# Schematic_AlchemyBoxSimple_2024-01-02.net
KiCad netlist of a schematic drawn in Altium Designer
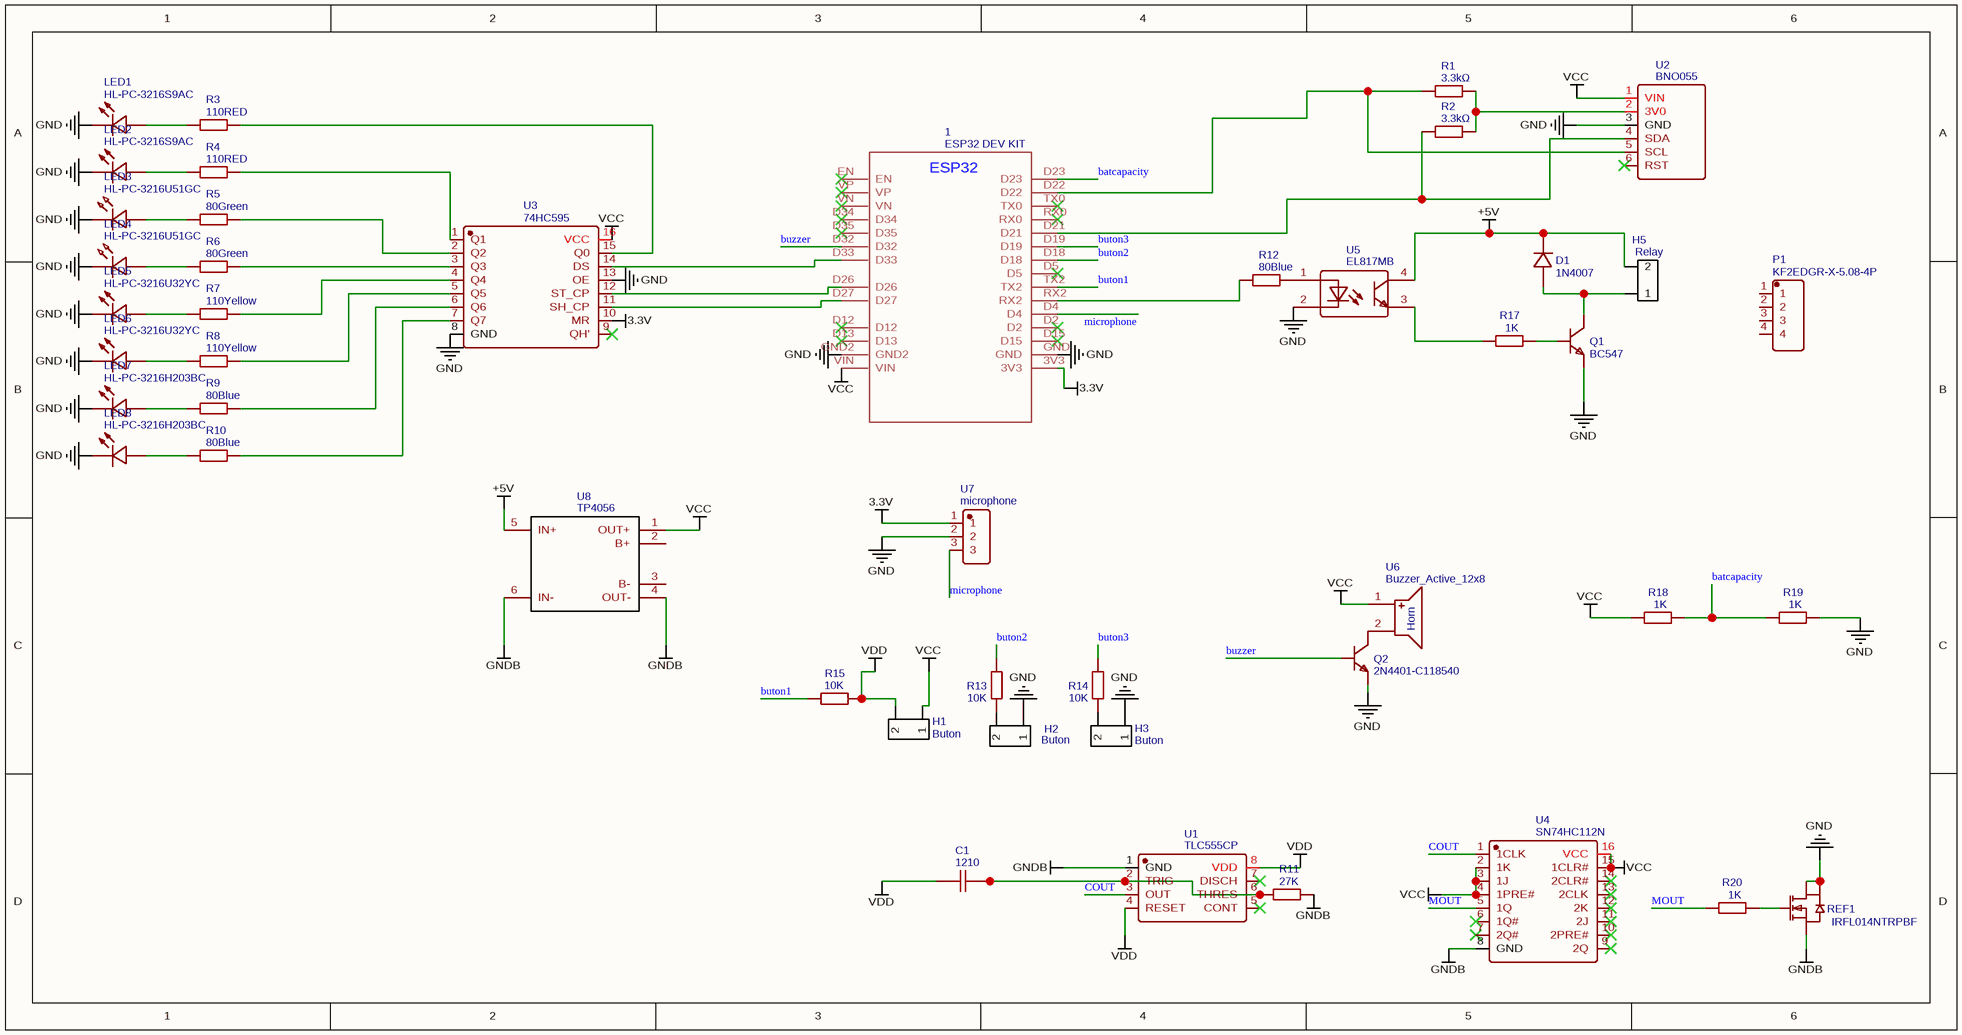
[diagram p0: Schematic_AlchemyBoxSimple_2024-01-02.schdoc]

(export (version "E")
  (design (tool "Eeschema 10.0.6"))
  (components
    (comp (ref "1")
      (value "ESP32 DEV KIT")
      (fields (field (name "CONTRIBUTOR") "u18040382"))
      (libsource (lib "altium-import") (part "root_0_ESP32 DEV KIT_"))
    )
    (comp (ref "C1")
      (value "1210")
      (fields (field (name "CONTRIBUTOR") "lcsc"))
      (libsource (lib "altium-import") (part "root_0_1210_"))
    )
    (comp (ref "D1")
      (value "1N4007")
      (fields (field (name "MANUFACTURER") "ST(先科)"))
      (libsource (lib "altium-import") (part "root_3_1N4007_"))
    )
    (comp (ref "H1")
      (value "Buton")
      (fields
        (field (name "MANUFACTURER") "BOOMELE")
        (field (name "MANUFACTURER PART") "Female headerHDR1X8-2.54")
        (field (name "CONTRIBUTOR") "kafikangi.m")
      )
      (libsource (lib "altium-import") (part "root_0_Buton_"))
    )
    (comp (ref "H2")
      (value "Buton")
      (fields
        (field (name "MANUFACTURER") "BOOMELE")
        (field (name "MANUFACTURER PART") "Female headerHDR1X8-2.54")
        (field (name "CONTRIBUTOR") "kafikangi.m")
      )
      (libsource (lib "altium-import") (part "root_0_Buton_"))
    )
    (comp (ref "H3")
      (value "Buton")
      (fields
        (field (name "MANUFACTURER") "BOOMELE")
        (field (name "MANUFACTURER PART") "Female headerHDR1X8-2.54")
        (field (name "CONTRIBUTOR") "kafikangi.m")
      )
      (libsource (lib "altium-import") (part "root_0_Buton_"))
    )
    (comp (ref "H5")
      (value "Relay")
      (fields
        (field (name "MANUFACTURER") "BOOMELE")
        (field (name "MANUFACTURER PART") "Female headerHDR1X8-2.54")
        (field (name "CONTRIBUTOR") "kafikangi.m")
      )
      (libsource (lib "altium-import") (part "root_1_Relay_"))
    )
    (comp (ref "LED1")
      (value "HL-PC-3216S9AC")
      (fields (field (name "MANUFACTURER") "HONGLITRONIC(鸿利光电)") (field (name "CONTRIBUTOR") "edfed"))
      (libsource (lib "altium-import") (part "root_0_HL-PC-3216S9AC_"))
    )
    (comp (ref "LED2")
      (value "HL-PC-3216S9AC")
      (fields (field (name "MANUFACTURER") "HONGLITRONIC(鸿利光电)") (field (name "CONTRIBUTOR") "edfed"))
      (libsource (lib "altium-import") (part "root_0_HL-PC-3216S9AC_"))
    )
    (comp (ref "LED3")
      (value "HL-PC-3216U51GC")
      (fields (field (name "MANUFACTURER") "HONGLITRONIC(鸿利光电)") (field (name "CONTRIBUTOR") "LCSC"))
      (libsource (lib "altium-import") (part "root_0_HL-PC-3216U51GC_"))
    )
    (comp (ref "LED4")
      (value "HL-PC-3216U51GC")
      (fields (field (name "MANUFACTURER") "HONGLITRONIC(鸿利光电)") (field (name "CONTRIBUTOR") "LCSC"))
      (libsource (lib "altium-import") (part "root_0_HL-PC-3216U51GC_"))
    )
    (comp (ref "LED5")
      (value "HL-PC-3216U32YC")
      (fields (field (name "MANUFACTURER") "HONGLITRONIC(鸿利光电)") (field (name "CONTRIBUTOR") "LCSC"))
      (libsource (lib "altium-import") (part "root_0_HL-PC-3216U32YC_"))
    )
    (comp (ref "LED6")
      (value "HL-PC-3216U32YC")
      (fields (field (name "MANUFACTURER") "HONGLITRONIC(鸿利光电)") (field (name "CONTRIBUTOR") "LCSC"))
      (libsource (lib "altium-import") (part "root_0_HL-PC-3216U32YC_"))
    )
    (comp (ref "LED7")
      (value "HL-PC-3216H203BC")
      (fields (field (name "MANUFACTURER") "HONGLITRONIC(鸿利光电)") (field (name "CONTRIBUTOR") "LCSC"))
      (libsource (lib "altium-import") (part "root_0_HL-PC-3216H203BC_"))
    )
    (comp (ref "LED8")
      (value "HL-PC-3216H203BC")
      (fields (field (name "MANUFACTURER") "HONGLITRONIC(鸿利光电)") (field (name "CONTRIBUTOR") "LCSC"))
      (libsource (lib "altium-import") (part "root_0_HL-PC-3216H203BC_"))
    )
    (comp (ref "P1")
      (value "KF2EDGR-X-5.08-4P")
      (fields (field (name "CONTRIBUTOR") "LCSC"))
      (libsource (lib "altium-import") (part "root_0_KF2EDGR-X-5.08-4P_"))
    )
    (comp (ref "Q1")
      (value "BC547")
      (fields (field (name "MANUFACTURER") "CJ(江苏长电/长晶)") (field (name "CONTRIBUTOR") "LCSC"))
      (libsource (lib "altium-import") (part "root_0_BC547_"))
    )
    (comp (ref "Q2")
      (value "2N4401-C118540")
      (fields
        (field (name "MANUFACTURER") "ST(先科)")
        (field (name "MANUFACTURER PART") "2N4401")
        (field (name "CONTRIBUTOR") "立创EDA官方封装库")
      )
      (libsource (lib "altium-import") (part "root_0_2N4401-C118540_"))
    )
    (comp (ref "R1")
      (value "3.3kΩ")
      (fields
        (field (name "MANUFACTURER") "Tyohm(幸亚电阻)")
        (field (name "MANUFACTURER PART") "RMC08053.3K1%N")
        (field (name "CONTRIBUTOR") "LCSC")
      )
      (libsource (lib "altium-import") (part "root_0_3.3kΩ_"))
    )
    (comp (ref "R2")
      (value "3.3kΩ")
      (fields
        (field (name "MANUFACTURER") "Tyohm(幸亚电阻)")
        (field (name "MANUFACTURER PART") "RMC08053.3K1%N")
        (field (name "CONTRIBUTOR") "LCSC")
      )
      (libsource (lib "altium-import") (part "root_0_3.3kΩ_"))
    )
    (comp (ref "R3")
      (value "110RED")
      (fields
        (field (name "MANUFACTURER") "YAGEO(国巨)")
        (field (name "MANUFACTURER PART") "RT0805FRD07100RL")
        (field (name "CONTRIBUTOR") "LCSC")
      )
      (libsource (lib "altium-import") (part "root_0_110RED_"))
    )
    (comp (ref "R4")
      (value "110RED")
      (fields
        (field (name "MANUFACTURER") "YAGEO(国巨)")
        (field (name "MANUFACTURER PART") "RT0805FRD07100RL")
        (field (name "CONTRIBUTOR") "LCSC")
      )
      (libsource (lib "altium-import") (part "root_0_110RED_"))
    )
    (comp (ref "R5")
      (value "80Green")
      (fields
        (field (name "MANUFACTURER") "YAGEO(国巨)")
        (field (name "MANUFACTURER PART") "RT0805FRD07100RL")
        (field (name "CONTRIBUTOR") "LCSC")
      )
      (libsource (lib "altium-import") (part "root_0_80Green_"))
    )
    (comp (ref "R6")
      (value "80Green")
      (fields
        (field (name "MANUFACTURER") "YAGEO(国巨)")
        (field (name "MANUFACTURER PART") "RT0805FRD07100RL")
        (field (name "CONTRIBUTOR") "LCSC")
      )
      (libsource (lib "altium-import") (part "root_0_80Green_"))
    )
    (comp (ref "R7")
      (value "110Yellow")
      (fields
        (field (name "MANUFACTURER") "YAGEO(国巨)")
        (field (name "MANUFACTURER PART") "RT0805FRD07100RL")
        (field (name "CONTRIBUTOR") "LCSC")
      )
      (libsource (lib "altium-import") (part "root_0_110Yellow_"))
    )
    (comp (ref "R8")
      (value "110Yellow")
      (fields
        (field (name "MANUFACTURER") "YAGEO(国巨)")
        (field (name "MANUFACTURER PART") "RT0805FRD07100RL")
        (field (name "CONTRIBUTOR") "LCSC")
      )
      (libsource (lib "altium-import") (part "root_0_110Yellow_"))
    )
    (comp (ref "R9")
      (value "80Blue")
      (fields
        (field (name "MANUFACTURER") "YAGEO(国巨)")
        (field (name "MANUFACTURER PART") "RT0805FRD07100RL")
        (field (name "CONTRIBUTOR") "LCSC")
      )
      (libsource (lib "altium-import") (part "root_0_80Blue_"))
    )
    (comp (ref "R10")
      (value "80Blue")
      (fields
        (field (name "MANUFACTURER") "YAGEO(国巨)")
        (field (name "MANUFACTURER PART") "RT0805FRD07100RL")
        (field (name "CONTRIBUTOR") "LCSC")
      )
      (libsource (lib "altium-import") (part "root_0_80Blue_"))
    )
    (comp (ref "R11")
      (value "27K")
      (fields
        (field (name "MANUFACTURER") "YAGEO(国巨)")
        (field (name "MANUFACTURER PART") "RT0805FRD07100RL")
        (field (name "CONTRIBUTOR") "LCSC")
      )
      (libsource (lib "altium-import") (part "root_0_27K_"))
    )
    (comp (ref "R12")
      (value "80Blue")
      (fields
        (field (name "MANUFACTURER") "YAGEO(国巨)")
        (field (name "MANUFACTURER PART") "RT0805FRD07100RL")
        (field (name "CONTRIBUTOR") "LCSC")
      )
      (libsource (lib "altium-import") (part "root_0_80Blue_"))
    )
    (comp (ref "R13")
      (value "10K")
      (fields
        (field (name "MANUFACTURER") "YAGEO(国巨)")
        (field (name "MANUFACTURER PART") "RT0805FRD07100RL")
        (field (name "CONTRIBUTOR") "LCSC")
      )
      (libsource (lib "altium-import") (part "root_3_10K_"))
    )
    (comp (ref "R14")
      (value "10K")
      (fields
        (field (name "MANUFACTURER") "YAGEO(国巨)")
        (field (name "MANUFACTURER PART") "RT0805FRD07100RL")
        (field (name "CONTRIBUTOR") "LCSC")
      )
      (libsource (lib "altium-import") (part "root_3_10K_"))
    )
    (comp (ref "R15")
      (value "10K")
      (fields
        (field (name "MANUFACTURER") "YAGEO(国巨)")
        (field (name "MANUFACTURER PART") "RT0805FRD07100RL")
        (field (name "CONTRIBUTOR") "LCSC")
      )
      (libsource (lib "altium-import") (part "root_2_10K_"))
    )
    (comp (ref "R17")
      (value "1K")
      (fields
        (field (name "MANUFACTURER") "YAGEO(国巨)")
        (field (name "MANUFACTURER PART") "RT0805FRD07100RL")
        (field (name "CONTRIBUTOR") "LCSC")
      )
      (libsource (lib "altium-import") (part "root_2_1K_"))
    )
    (comp (ref "R18")
      (value "1K")
      (fields
        (field (name "MANUFACTURER") "YAGEO(国巨)")
        (field (name "MANUFACTURER PART") "RT0805FRD07100RL")
        (field (name "CONTRIBUTOR") "LCSC")
      )
      (libsource (lib "altium-import") (part "root_2_1K_"))
    )
    (comp (ref "R19")
      (value "1K")
      (fields
        (field (name "MANUFACTURER") "YAGEO(国巨)")
        (field (name "MANUFACTURER PART") "RT0805FRD07100RL")
        (field (name "CONTRIBUTOR") "LCSC")
      )
      (libsource (lib "altium-import") (part "root_2_1K_"))
    )
    (comp (ref "R20")
      (value "1K")
      (fields
        (field (name "MANUFACTURER") "YAGEO(国巨)")
        (field (name "MANUFACTURER PART") "RT0805FRD07100RL")
        (field (name "CONTRIBUTOR") "LCSC")
      )
      (libsource (lib "altium-import") (part "root_2_1K_"))
    )
    (comp (ref "REF1")
      (value "IRFL014NTRPBF")
      (fields (field (name "MANUFACTURER") "Infineon(英飞凌)") (field (name "CONTRIBUTOR") "lcsc"))
      (libsource (lib "altium-import") (part "root_0_IRFL014NTRPBF_"))
    )
    (comp (ref "U1")
      (value "TLC555CP")
      (fields (field (name "MANUFACTURER") "TI(德州仪器)") (field (name "CONTRIBUTOR") "LCSC"))
      (libsource (lib "altium-import") (part "root_0_TLC555CP_"))
    )
    (comp (ref "U2")
      (value "BNO055")
      (fields (field (name "CONTRIBUTOR") "thipawan2112"))
      (libsource (lib "altium-import") (part "root_0_BNO055_"))
    )
    (comp (ref "U3")
      (value "74HC595")
      (fields (field (name "CONTRIBUTOR") "Thar Lin Htin"))
      (libsource (lib "altium-import") (part "root_0_74HC595_"))
    )
    (comp (ref "U4")
      (value "SN74HC112N")
      (fields (field (name "MANUFACTURER") "TI(德州仪器)") (field (name "CONTRIBUTOR") "LCSC"))
      (libsource (lib "altium-import") (part "root_0_SN74HC112N_"))
    )
    (comp (ref "U5")
      (value "EL817MB")
      (fields (field (name "MANUFACTURER") "EVERLIGHT(亿光)") (field (name "CONTRIBUTOR") "LCSC"))
      (libsource (lib "altium-import") (part "root_0_EL817MB_"))
    )
    (comp (ref "U6")
      (value "Buzzer_Active_12x8")
      (fields (field (name "CONTRIBUTOR") "jnnganga"))
      (libsource (lib "altium-import") (part "root_0_Buzzer_Active_12x8_"))
    )
    (comp (ref "U7")
      (value "microphone")
      (fields (field (name "MANUFACTURER PART") "2.54mm-1*3P 直针") (field (name "CONTRIBUTOR") "lcsc"))
      (libsource (lib "altium-import") (part "root_0_microphone_"))
    )
    (comp (ref "U8")
      (value "TP4056")
      (fields (field (name "CONTRIBUTOR") "jonathan.rama2005"))
      (libsource (lib "altium-import") (part "root_0_TP4056_"))
    )
  )
  (nets
    (net (code "1") (name "+5V") (class "Default")
      (node (ref "D1") (pin "1") (pinfunction "K_1") (pintype "passive"))
      (node (ref "H5") (pin "2") (pinfunction "2_2") (pintype "passive"))
      (node (ref "U5") (pin "4") (pinfunction "COL_4") (pintype "passive"))
      (node (ref "U8") (pin "5") (pinfunction "IN+_5") (pintype "passive"))
    )
    (net (code "2") (name "/COUT") (class "Default")
      (node (ref "U1") (pin "3") (pinfunction "OUT_3") (pintype "passive"))
      (node (ref "U4") (pin "1") (pinfunction "1CLK_1") (pintype "passive"))
    )
    (net (code "3") (name "/MOUT") (class "Default")
      (node (ref "R20") (pin "2") (pinfunction "2_2") (pintype "passive"))
      (node (ref "U4") (pin "5") (pinfunction "1Q_5") (pintype "passive"))
    )
    (net (code "4") (name "/batcapacity") (class "Default")
      (node (ref "1") (pin "D23") (pinfunction "D23_D23") (pintype "passive"))
      (node (ref "R18") (pin "1") (pinfunction "1_1") (pintype "passive"))
      (node (ref "R19") (pin "2") (pinfunction "2_2") (pintype "passive"))
    )
    (net (code "5") (name "/buton1") (class "Default")
      (node (ref "1") (pin "TX2") (pinfunction "TX2_TX2") (pintype "passive"))
      (node (ref "R15") (pin "2") (pinfunction "2_2") (pintype "passive"))
    )
    (net (code "6") (name "/buton2") (class "Default")
      (node (ref "1") (pin "D18") (pinfunction "D18_D18") (pintype "passive"))
      (node (ref "R13") (pin "1") (pinfunction "1_1") (pintype "passive"))
    )
    (net (code "7") (name "/buton3") (class "Default")
      (node (ref "1") (pin "D19") (pinfunction "D19_D19") (pintype "passive"))
      (node (ref "R14") (pin "1") (pinfunction "1_1") (pintype "passive"))
    )
    (net (code "8") (name "/buzzer") (class "Default")
      (node (ref "1") (pin "D32") (pinfunction "D32_D32") (pintype "passive"))
      (node (ref "Q2") (pin "2") (pinfunction "B_2") (pintype "passive"))
    )
    (net (code "9") (name "/microphone") (class "Default")
      (node (ref "1") (pin "D4") (pinfunction "D4_D4") (pintype "passive"))
      (node (ref "U7") (pin "3") (pinfunction "3_3") (pintype "passive"))
    )
    (net (code "10") (name "3.3V") (class "Default")
      (node (ref "1") (pin "3V3") (pinfunction "3V3_3V3") (pintype "passive"))
      (node (ref "U3") (pin "10") (pinfunction "MR_10") (pintype "passive"))
      (node (ref "U7") (pin "1") (pinfunction "1_1") (pintype "passive"))
    )
    (net (code "11") (name "GND") (class "Default")
      (node (ref "1") (pin "GND") (pinfunction "GND_GND") (pintype "passive"))
      (node (ref "1") (pin "GND2") (pinfunction "GND2_GND2") (pintype "passive"))
      (node (ref "H2") (pin "1") (pinfunction "1_1") (pintype "passive"))
      (node (ref "H3") (pin "1") (pinfunction "1_1") (pintype "passive"))
      (node (ref "LED1") (pin "2") (pinfunction "K_2") (pintype "passive"))
      (node (ref "LED2") (pin "2") (pinfunction "K_2") (pintype "passive"))
      (node (ref "LED3") (pin "1") (pinfunction "1_1") (pintype "passive"))
      (node (ref "LED4") (pin "1") (pinfunction "1_1") (pintype "passive"))
      (node (ref "LED5") (pin "1") (pinfunction "C_1") (pintype "passive"))
      (node (ref "LED6") (pin "1") (pinfunction "C_1") (pintype "passive"))
      (node (ref "LED7") (pin "2") (pinfunction "K_2") (pintype "passive"))
      (node (ref "LED8") (pin "2") (pinfunction "K_2") (pintype "passive"))
      (node (ref "Q1") (pin "3") (pinfunction "E_3") (pintype "passive"))
      (node (ref "Q2") (pin "1") (pinfunction "E_1") (pintype "passive"))
      (node (ref "R19") (pin "1") (pinfunction "1_1") (pintype "passive"))
      (node (ref "REF1") (pin "2") (pinfunction "D_2") (pintype "passive"))
      (node (ref "REF1") (pin "4") (pinfunction "D_4") (pintype "passive"))
      (node (ref "U2") (pin "3") (pinfunction "GND_3") (pintype "passive"))
      (node (ref "U3") (pin "13") (pinfunction "OE_13") (pintype "passive"))
      (node (ref "U3") (pin "8") (pinfunction "GND_8") (pintype "passive"))
      (node (ref "U5") (pin "2") (pinfunction "CAT_2") (pintype "passive"))
      (node (ref "U7") (pin "2") (pinfunction "2_2") (pintype "passive"))
    )
    (net (code "12") (name "GNDB") (class "Default")
      (node (ref "R11") (pin "2") (pinfunction "2_2") (pintype "passive"))
      (node (ref "REF1") (pin "3") (pinfunction "S_3") (pintype "passive"))
      (node (ref "U1") (pin "1") (pinfunction "GND_1") (pintype "passive"))
      (node (ref "U4") (pin "8") (pinfunction "GND_8") (pintype "passive"))
      (node (ref "U8") (pin "4") (pinfunction "OUT-_4") (pintype "passive"))
      (node (ref "U8") (pin "6") (pinfunction "IN-_6") (pintype "passive"))
    )
    (net (code "13") (name "Net-(1-PadRX2)") (class "Default")
      (node (ref "1") (pin "RX2") (pinfunction "RX2_RX2") (pintype "passive"))
      (node (ref "R12") (pin "1") (pinfunction "1_1") (pintype "passive"))
    )
    (net (code "14") (name "Net-(D1-A)") (class "Default")
      (node (ref "D1") (pin "2") (pinfunction "A_2") (pintype "passive"))
      (node (ref "H5") (pin "1") (pinfunction "1_1") (pintype "passive"))
      (node (ref "Q1") (pin "1") (pinfunction "C_1") (pintype "passive"))
    )
    (net (code "15") (name "Net-(H2-Pad2)") (class "Default")
      (node (ref "H2") (pin "2") (pinfunction "2_2") (pintype "passive"))
      (node (ref "R13") (pin "2") (pinfunction "2_2") (pintype "passive"))
    )
    (net (code "16") (name "Net-(H3-Pad2)") (class "Default")
      (node (ref "H3") (pin "2") (pinfunction "2_2") (pintype "passive"))
      (node (ref "R14") (pin "2") (pinfunction "2_2") (pintype "passive"))
    )
    (net (code "17") (name "Net-(LED1-A)") (class "Default")
      (node (ref "LED1") (pin "1") (pinfunction "A_1") (pintype "passive"))
      (node (ref "R3") (pin "1") (pinfunction "1_1") (pintype "passive"))
    )
    (net (code "18") (name "Net-(LED2-A)") (class "Default")
      (node (ref "LED2") (pin "1") (pinfunction "A_1") (pintype "passive"))
      (node (ref "R4") (pin "1") (pinfunction "1_1") (pintype "passive"))
    )
    (net (code "19") (name "Net-(LED3-Pad2)") (class "Default")
      (node (ref "LED3") (pin "2") (pinfunction "2_2") (pintype "passive"))
      (node (ref "R5") (pin "1") (pinfunction "1_1") (pintype "passive"))
    )
    (net (code "20") (name "Net-(LED4-Pad2)") (class "Default")
      (node (ref "LED4") (pin "2") (pinfunction "2_2") (pintype "passive"))
      (node (ref "R6") (pin "1") (pinfunction "1_1") (pintype "passive"))
    )
    (net (code "21") (name "Net-(LED5-A)") (class "Default")
      (node (ref "LED5") (pin "2") (pinfunction "A_2") (pintype "passive"))
      (node (ref "R7") (pin "1") (pinfunction "1_1") (pintype "passive"))
    )
    (net (code "22") (name "Net-(LED6-A)") (class "Default")
      (node (ref "LED6") (pin "2") (pinfunction "A_2") (pintype "passive"))
      (node (ref "R8") (pin "1") (pinfunction "1_1") (pintype "passive"))
    )
    (net (code "23") (name "Net-(LED7-A)") (class "Default")
      (node (ref "LED7") (pin "1") (pinfunction "A_1") (pintype "passive"))
      (node (ref "R9") (pin "1") (pinfunction "1_1") (pintype "passive"))
    )
    (net (code "24") (name "Net-(LED8-A)") (class "Default")
      (node (ref "LED8") (pin "1") (pinfunction "A_1") (pintype "passive"))
      (node (ref "R10") (pin "1") (pinfunction "1_1") (pintype "passive"))
    )
    (net (code "25") (name "Net-(Q1-B)") (class "Default")
      (node (ref "Q1") (pin "2") (pinfunction "B_2") (pintype "passive"))
      (node (ref "R17") (pin "1") (pinfunction "1_1") (pintype "passive"))
    )
    (net (code "26") (name "Net-(Q2-C)") (class "Default")
      (node (ref "Q2") (pin "3") (pinfunction "C_3") (pintype "passive"))
      (node (ref "U6") (pin "2") (pinfunction "2_2") (pintype "passive"))
    )
    (net (code "27") (name "Net-(REF1-G)") (class "Default")
      (node (ref "R20") (pin "1") (pinfunction "1_1") (pintype "passive"))
      (node (ref "REF1") (pin "1") (pinfunction "G_1") (pintype "passive"))
    )
    (net (code "28") (name "Net-(U1-THRES)") (class "Default")
      (node (ref "C1") (pin "2") (pinfunction "2_2") (pintype "passive"))
      (node (ref "R11") (pin "1") (pinfunction "1_1") (pintype "passive"))
      (node (ref "U1") (pin "2") (pinfunction "TRIG_2") (pintype "passive"))
      (node (ref "U1") (pin "6") (pinfunction "THRES_6") (pintype "passive"))
    )
    (net (code "29") (name "Net-(U2-3V0)") (class "Default")
      (node (ref "R1") (pin "2") (pinfunction "2_2") (pintype "passive"))
      (node (ref "R2") (pin "2") (pinfunction "2_2") (pintype "passive"))
      (node (ref "U2") (pin "2") (pinfunction "3V0_2") (pintype "passive"))
    )
    (net (code "30") (name "Net-(U2-SCL)") (class "Default")
      (node (ref "1") (pin "D22") (pinfunction "D22_D22") (pintype "passive"))
      (node (ref "R1") (pin "1") (pinfunction "1_1") (pintype "passive"))
      (node (ref "U2") (pin "5") (pinfunction "SCL_5") (pintype "passive"))
    )
    (net (code "31") (name "Net-(U2-SDA)") (class "Default")
      (node (ref "1") (pin "D21") (pinfunction "D21_D21") (pintype "passive"))
      (node (ref "R2") (pin "1") (pinfunction "1_1") (pintype "passive"))
      (node (ref "U2") (pin "4") (pinfunction "SDA_4") (pintype "passive"))
    )
    (net (code "32") (name "Net-(U3-DS)") (class "Default")
      (node (ref "1") (pin "D33") (pinfunction "D33_D33") (pintype "passive"))
      (node (ref "U3") (pin "14") (pinfunction "DS_14") (pintype "passive"))
    )
    (net (code "33") (name "Net-(U3-Q0)") (class "Default")
      (node (ref "R3") (pin "2") (pinfunction "2_2") (pintype "passive"))
      (node (ref "U3") (pin "15") (pinfunction "Q0_15") (pintype "passive"))
    )
    (net (code "34") (name "Net-(U3-Q1)") (class "Default")
      (node (ref "R4") (pin "2") (pinfunction "2_2") (pintype "passive"))
      (node (ref "U3") (pin "1") (pinfunction "Q1_1") (pintype "passive"))
    )
    (net (code "35") (name "Net-(U3-Q2)") (class "Default")
      (node (ref "R5") (pin "2") (pinfunction "2_2") (pintype "passive"))
      (node (ref "U3") (pin "2") (pinfunction "Q2_2") (pintype "passive"))
    )
    (net (code "36") (name "Net-(U3-Q3)") (class "Default")
      (node (ref "R6") (pin "2") (pinfunction "2_2") (pintype "passive"))
      (node (ref "U3") (pin "3") (pinfunction "Q3_3") (pintype "passive"))
    )
    (net (code "37") (name "Net-(U3-Q4)") (class "Default")
      (node (ref "R7") (pin "2") (pinfunction "2_2") (pintype "passive"))
      (node (ref "U3") (pin "4") (pinfunction "Q4_4") (pintype "passive"))
    )
    (net (code "38") (name "Net-(U3-Q5)") (class "Default")
      (node (ref "R8") (pin "2") (pinfunction "2_2") (pintype "passive"))
      (node (ref "U3") (pin "5") (pinfunction "Q5_5") (pintype "passive"))
    )
    (net (code "39") (name "Net-(U3-Q6)") (class "Default")
      (node (ref "R9") (pin "2") (pinfunction "2_2") (pintype "passive"))
      (node (ref "U3") (pin "6") (pinfunction "Q6_6") (pintype "passive"))
    )
    (net (code "40") (name "Net-(U3-Q7)") (class "Default")
      (node (ref "R10") (pin "2") (pinfunction "2_2") (pintype "passive"))
      (node (ref "U3") (pin "7") (pinfunction "Q7_7") (pintype "passive"))
    )
    (net (code "41") (name "Net-(U3-SH_CP)") (class "Default")
      (node (ref "1") (pin "D27") (pinfunction "D27_D27") (pintype "passive"))
      (node (ref "U3") (pin "11") (pinfunction "SH_CP_11") (pintype "passive"))
    )
    (net (code "42") (name "Net-(U3-ST_CP)") (class "Default")
      (node (ref "1") (pin "D26") (pinfunction "D26_D26") (pintype "passive"))
      (node (ref "U3") (pin "12") (pinfunction "ST_CP_12") (pintype "passive"))
    )
    (net (code "43") (name "Net-(U5-AN)") (class "Default")
      (node (ref "R12") (pin "2") (pinfunction "2_2") (pintype "passive"))
      (node (ref "U5") (pin "1") (pinfunction "AN_1") (pintype "passive"))
    )
    (net (code "44") (name "Net-(U5-EM)") (class "Default")
      (node (ref "R17") (pin "2") (pinfunction "2_2") (pintype "passive"))
      (node (ref "U5") (pin "3") (pinfunction "EM_3") (pintype "passive"))
    )
    (net (code "45") (name "VCC") (class "Default")
      (node (ref "1") (pin "VIN") (pinfunction "VIN_VIN") (pintype "passive"))
      (node (ref "H1") (pin "1") (pinfunction "1_1") (pintype "passive"))
      (node (ref "R18") (pin "2") (pinfunction "2_2") (pintype "passive"))
      (node (ref "U2") (pin "1") (pinfunction "VIN_1") (pintype "passive"))
      (node (ref "U3") (pin "16") (pinfunction "VCC_16") (pintype "passive"))
      (node (ref "U4") (pin "15") (pinfunction "1CLR#_15") (pintype "passive"))
      (node (ref "U4") (pin "16") (pinfunction "VCC_16") (pintype "passive"))
      (node (ref "U4") (pin "2") (pinfunction "1K_2") (pintype "passive"))
      (node (ref "U4") (pin "3") (pinfunction "1J_3") (pintype "passive"))
      (node (ref "U4") (pin "4") (pinfunction "1PRE#_4") (pintype "passive"))
      (node (ref "U6") (pin "1") (pinfunction "1_1") (pintype "passive"))
      (node (ref "U8") (pin "1") (pinfunction "OUT+_1") (pintype "passive"))
    )
    (net (code "46") (name "VDD") (class "Default")
      (node (ref "C1") (pin "1") (pinfunction "1_1") (pintype "passive"))
      (node (ref "H1") (pin "2") (pinfunction "2_2") (pintype "passive"))
      (node (ref "R15") (pin "1") (pinfunction "1_1") (pintype "passive"))
      (node (ref "U1") (pin "4") (pinfunction "RESET_4") (pintype "passive"))
      (node (ref "U1") (pin "8") (pinfunction "VDD_8") (pintype "passive"))
    )
    (net (code "47") (name "unconnected-(1-PadD2)") (class "Default")
      (node (ref "1") (pin "D2") (pinfunction "D2_D2") (pintype "passive+no_connect"))
    )
    (net (code "48") (name "unconnected-(1-PadD5)") (class "Default")
      (node (ref "1") (pin "D5") (pinfunction "D5_D5") (pintype "passive+no_connect"))
    )
    (net (code "49") (name "unconnected-(1-PadD12)") (class "Default")
      (node (ref "1") (pin "D12") (pinfunction "D12_D12") (pintype "passive+no_connect"))
    )
    (net (code "50") (name "unconnected-(1-PadD13)") (class "Default")
      (node (ref "1") (pin "D13") (pinfunction "D13_D13") (pintype "passive+no_connect"))
    )
    (net (code "51") (name "unconnected-(1-PadD15)") (class "Default")
      (node (ref "1") (pin "D15") (pinfunction "D15_D15") (pintype "passive+no_connect"))
    )
    (net (code "52") (name "unconnected-(1-PadD34)") (class "Default")
      (node (ref "1") (pin "D34") (pinfunction "D34_D34") (pintype "passive+no_connect"))
    )
    (net (code "53") (name "unconnected-(1-PadD35)") (class "Default")
      (node (ref "1") (pin "D35") (pinfunction "D35_D35") (pintype "passive+no_connect"))
    )
    (net (code "54") (name "unconnected-(1-PadEN)") (class "Default")
      (node (ref "1") (pin "EN") (pinfunction "EN_EN") (pintype "passive+no_connect"))
    )
    (net (code "55") (name "unconnected-(1-PadRX0)") (class "Default")
      (node (ref "1") (pin "RX0") (pinfunction "RX0_RX0") (pintype "passive+no_connect"))
    )
    (net (code "56") (name "unconnected-(1-PadTX0)") (class "Default")
      (node (ref "1") (pin "TX0") (pinfunction "TX0_TX0") (pintype "passive+no_connect"))
    )
    (net (code "57") (name "unconnected-(1-PadVN)") (class "Default")
      (node (ref "1") (pin "VN") (pinfunction "VN_VN") (pintype "passive+no_connect"))
    )
    (net (code "58") (name "unconnected-(1-PadVP)") (class "Default")
      (node (ref "1") (pin "VP") (pinfunction "VP_VP") (pintype "passive+no_connect"))
    )
    (net (code "59") (name "unconnected-(P1-Pad1)") (class "Default")
      (node (ref "P1") (pin "1") (pinfunction "1_1") (pintype "passive"))
    )
    (net (code "60") (name "unconnected-(P1-Pad2)") (class "Default")
      (node (ref "P1") (pin "2") (pinfunction "2_2") (pintype "passive"))
    )
    (net (code "61") (name "unconnected-(P1-Pad3)") (class "Default")
      (node (ref "P1") (pin "3") (pinfunction "3_3") (pintype "passive"))
    )
    (net (code "62") (name "unconnected-(P1-Pad4)") (class "Default")
      (node (ref "P1") (pin "4") (pinfunction "4_4") (pintype "passive"))
    )
    (net (code "63") (name "unconnected-(U1-CONT-Pad5)") (class "Default")
      (node (ref "U1") (pin "5") (pinfunction "CONT_5") (pintype "passive+no_connect"))
    )
    (net (code "64") (name "unconnected-(U1-DISCH-Pad7)") (class "Default")
      (node (ref "U1") (pin "7") (pinfunction "DISCH_7") (pintype "passive+no_connect"))
    )
    (net (code "65") (name "unconnected-(U2-RST-Pad6)") (class "Default")
      (node (ref "U2") (pin "6") (pinfunction "RST_6") (pintype "passive+no_connect"))
    )
    (net (code "66") (name "unconnected-(U3-QH'-Pad9)") (class "Default")
      (node (ref "U3") (pin "9") (pinfunction "QH'_9") (pintype "passive+no_connect"))
    )
    (net (code "67") (name "unconnected-(U4-1Q#-Pad6)") (class "Default")
      (node (ref "U4") (pin "6") (pinfunction "1Q#_6") (pintype "passive+no_connect"))
    )
    (net (code "68") (name "unconnected-(U4-2CLK-Pad13)") (class "Default")
      (node (ref "U4") (pin "13") (pinfunction "2CLK_13") (pintype "passive+no_connect"))
    )
    (net (code "69") (name "unconnected-(U4-2CLR#-Pad14)") (class "Default")
      (node (ref "U4") (pin "14") (pinfunction "2CLR#_14") (pintype "passive+no_connect"))
    )
    (net (code "70") (name "unconnected-(U4-2J-Pad11)") (class "Default")
      (node (ref "U4") (pin "11") (pinfunction "2J_11") (pintype "passive+no_connect"))
    )
    (net (code "71") (name "unconnected-(U4-2K-Pad12)") (class "Default")
      (node (ref "U4") (pin "12") (pinfunction "2K_12") (pintype "passive+no_connect"))
    )
    (net (code "72") (name "unconnected-(U4-2PRE#-Pad10)") (class "Default")
      (node (ref "U4") (pin "10") (pinfunction "2PRE#_10") (pintype "passive+no_connect"))
    )
    (net (code "73") (name "unconnected-(U4-2Q#-Pad7)") (class "Default")
      (node (ref "U4") (pin "7") (pinfunction "2Q#_7") (pintype "passive+no_connect"))
    )
    (net (code "74") (name "unconnected-(U4-2Q-Pad9)") (class "Default")
      (node (ref "U4") (pin "9") (pinfunction "2Q_9") (pintype "passive+no_connect"))
    )
    (net (code "75") (name "unconnected-(U8-B+-Pad2)") (class "Default")
      (node (ref "U8") (pin "2") (pinfunction "B+_2") (pintype "passive"))
    )
    (net (code "76") (name "unconnected-(U8-B--Pad3)") (class "Default")
      (node (ref "U8") (pin "3") (pinfunction "B-_3") (pintype "passive"))
    )
  )
)
